# ESP32-WROOM-32.net
KiCad netlist of a schematic drawn in Altium Designer
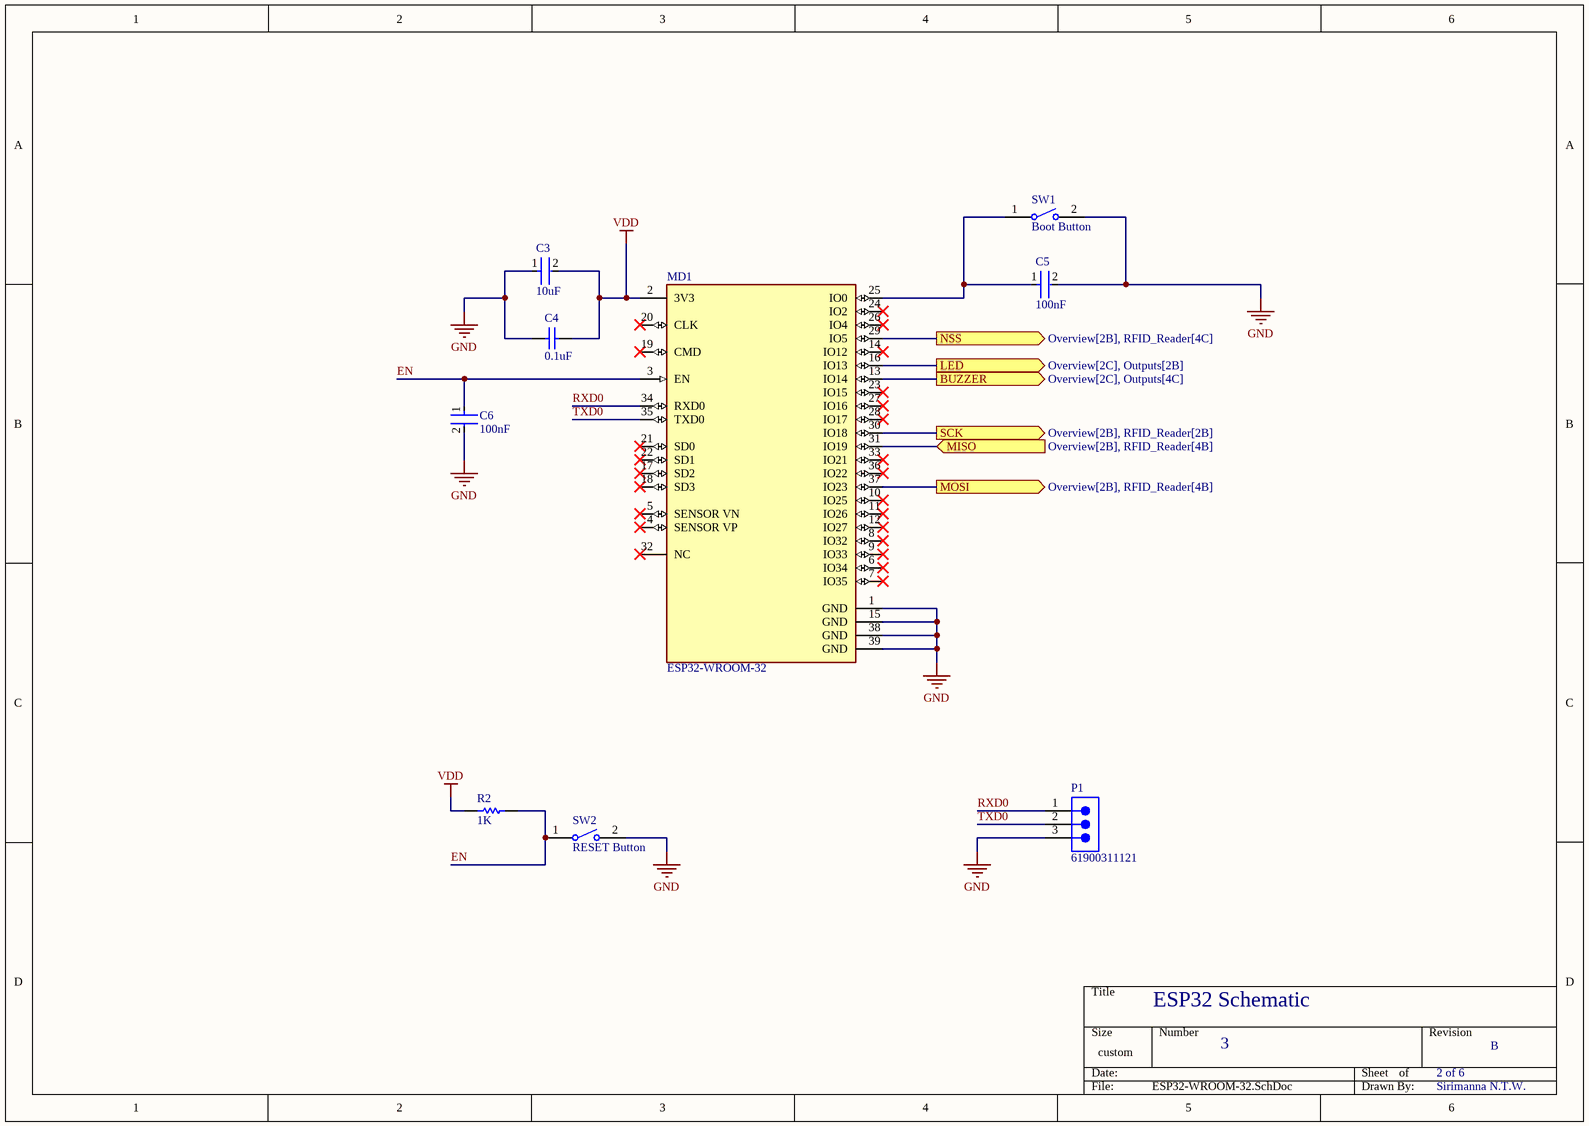
[diagram p0: ESP32-WROOM-32.SchDoc]

(export (version "E")
  (design (tool "Eeschema 10.0.6"))
  (components
    (comp (ref "C3")
      (value "10uF")
      (footprint "FP-C0805C-DG-MFG")
      (description "CAP CER 10UF 10V X5R 0805")
      (fields (field (name "TOLERANCE") "10%") (field (name "MANUFACTURER PART NUMBER") "C0805C106K8PACTU"))
      (libsource (lib "Altium Content Vault") (part "11868f565c42a9108669ba33697ecf6"))
    )
    (comp (ref "C4")
      (value "0.1uF")
      (footprint "CAPC2013X94X50ML20T25")
      (fields
        (field (name "MANUFACTURER") "AVX Interconnect / Elco")
        (field (name "PART NUMBER") "08051C104JAT2A")
      )
      (libsource (lib "Altium Content Vault") (part "CAP"))
    )
    (comp (ref "C5")
      (value "100nF")
      (footprint "FP-CC0805-0_85-MFG")
      (description "CAP CER 0.1UF 50V X7R 0805")
      (fields (field (name "TOLERANCE") "0.1") (field (name "MANUFACTURER PART NUMBER") "CC0805KRX7R9BB104"))
      (libsource (lib "Altium Content Vault") (part "11868f565c42a9108669ba33697ecf6"))
    )
    (comp (ref "C6")
      (value "100nF")
      (footprint "FP-0805-L_2_01_0_2-W_1_25-IPC_B")
      (description "General Purpose Ceramic Capacitor, 0805, 100nF, 10%, X7R, 15%, 100V")
      (fields (field (name "VOLTAGE") "100V") (field (name "TOLERANCE") "10%"))
      (libsource (lib "Altium Content Vault") (part "b4654b650e69147ec39a6b967a45e02"))
    )
    (comp (ref "MD1")
      (value "ESP32-WROOM-32")
      (footprint "FP-ESP32-WROOM-32-MFG")
      (description "RX TXRX MOD WIFI SURFACE MOUNT")
      (libsource (lib "Altium Content Vault") (part "ee866abf0b6c51247b7f5cdebf2f250"))
    )
    (comp (ref "P1")
      (value "61900311121")
      (footprint "61900311121")
      (libsource (lib "Altium Content Vault") (part "Header_Male_1R_03P"))
    )
    (comp (ref "R2")
      (value "1K")
      (footprint "RESC2013X60X35ML10T20")
      (description "Chip Resistor, 1 KOhm, +/- 1%, 125 mW, -55 to 155 degC, 0805 (2012 Metric), RoHS, Tape and Reel")
      (fields (field (name "TOLERANCE") "1%") (field (name "MANUFACTURER") "Yageo"))
      (libsource (lib "Altium Content Vault") (part "RES-2"))
    )
    (comp (ref "SW1")
      (value "Boot Button")
      (footprint "TECO-FSMSM-2_V")
      (description "FSMSM Push Button Switch, 50 mA, -35 to 85 degC, 2-Pin SMD, RoHS, Bulk")
      (fields (field (name "MANUFACTURER") "TE Connectivity"))
      (libsource (lib "Altium Content Vault") (part "SW-SPST-2_C"))
    )
    (comp (ref "SW2")
      (value "RESET Button")
      (footprint "TECO-FSMSM-2_V")
      (description "FSMSM Push Button Switch, 50 mA, -35 to 85 degC, 2-Pin SMD, RoHS, Bulk")
      (fields (field (name "MANUFACTURER") "TE Connectivity"))
      (libsource (lib "Altium Content Vault") (part "SW-SPST-2_C"))
    )
  )
  (nets
    (net (code "1") (name "/BUZZER") (class "Default")
      (node (ref "MD1") (pin "13") (pinfunction "IO14_13") (pintype "bidirectional"))
    )
    (net (code "2") (name "/EN") (class "Default")
      (node (ref "C6") (pin "1") (pinfunction "1_1") (pintype "passive"))
      (node (ref "MD1") (pin "3") (pinfunction "EN_3") (pintype "input"))
      (node (ref "R2") (pin "2") (pinfunction "2_2") (pintype "passive"))
      (node (ref "SW2") (pin "1") (pinfunction "1_1") (pintype "passive"))
    )
    (net (code "3") (name "/LED") (class "Default")
      (node (ref "MD1") (pin "16") (pinfunction "IO13_16") (pintype "bidirectional"))
    )
    (net (code "4") (name "/MISO") (class "Default")
      (node (ref "MD1") (pin "31") (pinfunction "IO19_31") (pintype "bidirectional"))
    )
    (net (code "5") (name "/MOSI") (class "Default")
      (node (ref "MD1") (pin "37") (pinfunction "IO23_37") (pintype "bidirectional"))
    )
    (net (code "6") (name "/NSS") (class "Default")
      (node (ref "MD1") (pin "29") (pinfunction "IO5_29") (pintype "bidirectional"))
    )
    (net (code "7") (name "/RXD0") (class "Default")
      (node (ref "MD1") (pin "34") (pinfunction "RXD0_34") (pintype "bidirectional"))
      (node (ref "P1") (pin "1") (pinfunction "1_1") (pintype "passive"))
    )
    (net (code "8") (name "/SCK") (class "Default")
      (node (ref "MD1") (pin "30") (pinfunction "IO18_30") (pintype "bidirectional"))
    )
    (net (code "9") (name "/TXD0") (class "Default")
      (node (ref "MD1") (pin "35") (pinfunction "TXD0_35") (pintype "bidirectional"))
      (node (ref "P1") (pin "2") (pinfunction "2_2") (pintype "passive"))
    )
    (net (code "10") (name "GND") (class "Default")
      (node (ref "C3") (pin "1") (pinfunction "1_1") (pintype "passive"))
      (node (ref "C4") (pin "1") (pinfunction "1_1") (pintype "passive"))
      (node (ref "C5") (pin "2") (pinfunction "2_2") (pintype "passive"))
      (node (ref "C6") (pin "2") (pinfunction "2_2") (pintype "passive"))
      (node (ref "MD1") (pin "1") (pinfunction "GND_1") (pintype "power_in"))
      (node (ref "MD1") (pin "15") (pinfunction "GND_15") (pintype "power_in"))
      (node (ref "MD1") (pin "38") (pinfunction "GND_38") (pintype "power_in"))
      (node (ref "MD1") (pin "39") (pinfunction "GND_39") (pintype "power_in"))
      (node (ref "P1") (pin "3") (pinfunction "3_3") (pintype "passive"))
      (node (ref "SW1") (pin "2") (pinfunction "2_2") (pintype "passive"))
      (node (ref "SW2") (pin "2") (pinfunction "2_2") (pintype "passive"))
    )
    (net (code "11") (name "Net-(MD1-IO0)") (class "Default")
      (node (ref "C5") (pin "1") (pinfunction "1_1") (pintype "passive"))
      (node (ref "MD1") (pin "25") (pinfunction "IO0_25") (pintype "bidirectional"))
      (node (ref "SW1") (pin "1") (pinfunction "1_1") (pintype "passive"))
    )
    (net (code "12") (name "VDD") (class "Default")
      (node (ref "C3") (pin "2") (pinfunction "2_2") (pintype "passive"))
      (node (ref "C4") (pin "2") (pinfunction "2_2") (pintype "passive"))
      (node (ref "MD1") (pin "2") (pinfunction "3V3_2") (pintype "power_in"))
      (node (ref "R2") (pin "1") (pinfunction "1_1") (pintype "passive"))
    )
    (net (code "13") (name "unconnected-(MD1-CLK-Pad20)") (class "Default")
      (node (ref "MD1") (pin "20") (pinfunction "CLK_20") (pintype "bidirectional+no_connect"))
    )
    (net (code "14") (name "unconnected-(MD1-CMD-Pad19)") (class "Default")
      (node (ref "MD1") (pin "19") (pinfunction "CMD_19") (pintype "bidirectional+no_connect"))
    )
    (net (code "15") (name "unconnected-(MD1-IO2-Pad24)") (class "Default")
      (node (ref "MD1") (pin "24") (pinfunction "IO2_24") (pintype "bidirectional+no_connect"))
    )
    (net (code "16") (name "unconnected-(MD1-IO4-Pad26)") (class "Default")
      (node (ref "MD1") (pin "26") (pinfunction "IO4_26") (pintype "bidirectional+no_connect"))
    )
    (net (code "17") (name "unconnected-(MD1-IO12-Pad14)") (class "Default")
      (node (ref "MD1") (pin "14") (pinfunction "IO12_14") (pintype "bidirectional+no_connect"))
    )
    (net (code "18") (name "unconnected-(MD1-IO15-Pad23)") (class "Default")
      (node (ref "MD1") (pin "23") (pinfunction "IO15_23") (pintype "bidirectional+no_connect"))
    )
    (net (code "19") (name "unconnected-(MD1-IO16-Pad27)") (class "Default")
      (node (ref "MD1") (pin "27") (pinfunction "IO16_27") (pintype "bidirectional+no_connect"))
    )
    (net (code "20") (name "unconnected-(MD1-IO17-Pad28)") (class "Default")
      (node (ref "MD1") (pin "28") (pinfunction "IO17_28") (pintype "bidirectional+no_connect"))
    )
    (net (code "21") (name "unconnected-(MD1-IO21-Pad33)") (class "Default")
      (node (ref "MD1") (pin "33") (pinfunction "IO21_33") (pintype "bidirectional+no_connect"))
    )
    (net (code "22") (name "unconnected-(MD1-IO22-Pad36)") (class "Default")
      (node (ref "MD1") (pin "36") (pinfunction "IO22_36") (pintype "bidirectional+no_connect"))
    )
    (net (code "23") (name "unconnected-(MD1-IO25-Pad10)") (class "Default")
      (node (ref "MD1") (pin "10") (pinfunction "IO25_10") (pintype "bidirectional+no_connect"))
    )
    (net (code "24") (name "unconnected-(MD1-IO26-Pad11)") (class "Default")
      (node (ref "MD1") (pin "11") (pinfunction "IO26_11") (pintype "bidirectional+no_connect"))
    )
    (net (code "25") (name "unconnected-(MD1-IO27-Pad12)") (class "Default")
      (node (ref "MD1") (pin "12") (pinfunction "IO27_12") (pintype "bidirectional+no_connect"))
    )
    (net (code "26") (name "unconnected-(MD1-IO32-Pad8)") (class "Default")
      (node (ref "MD1") (pin "8") (pinfunction "IO32_8") (pintype "bidirectional+no_connect"))
    )
    (net (code "27") (name "unconnected-(MD1-IO33-Pad9)") (class "Default")
      (node (ref "MD1") (pin "9") (pinfunction "IO33_9") (pintype "bidirectional+no_connect"))
    )
    (net (code "28") (name "unconnected-(MD1-IO34-Pad6)") (class "Default")
      (node (ref "MD1") (pin "6") (pinfunction "IO34_6") (pintype "bidirectional+no_connect"))
    )
    (net (code "29") (name "unconnected-(MD1-IO35-Pad7)") (class "Default")
      (node (ref "MD1") (pin "7") (pinfunction "IO35_7") (pintype "bidirectional+no_connect"))
    )
    (net (code "30") (name "unconnected-(MD1-NC-Pad32)") (class "Default")
      (node (ref "MD1") (pin "32") (pinfunction "NC_32") (pintype "passive+no_connect"))
    )
    (net (code "31") (name "unconnected-(MD1-SD0-Pad21)") (class "Default")
      (node (ref "MD1") (pin "21") (pinfunction "SD0_21") (pintype "bidirectional+no_connect"))
    )
    (net (code "32") (name "unconnected-(MD1-SD1-Pad22)") (class "Default")
      (node (ref "MD1") (pin "22") (pinfunction "SD1_22") (pintype "bidirectional+no_connect"))
    )
    (net (code "33") (name "unconnected-(MD1-SD2-Pad17)") (class "Default")
      (node (ref "MD1") (pin "17") (pinfunction "SD2_17") (pintype "bidirectional+no_connect"))
    )
    (net (code "34") (name "unconnected-(MD1-SD3-Pad18)") (class "Default")
      (node (ref "MD1") (pin "18") (pinfunction "SD3_18") (pintype "bidirectional+no_connect"))
    )
    (net (code "35") (name "unconnected-(MD1-SENSOR_VN-Pad5)") (class "Default")
      (node (ref "MD1") (pin "5") (pinfunction "SENSOR_VN_5") (pintype "bidirectional+no_connect"))
    )
    (net (code "36") (name "unconnected-(MD1-SENSOR_VP-Pad4)") (class "Default")
      (node (ref "MD1") (pin "4") (pinfunction "SENSOR_VP_4") (pintype "bidirectional+no_connect"))
    )
  )
)
